# microcontroller.net
KiCad netlist of a schematic drawn in Altium Designer
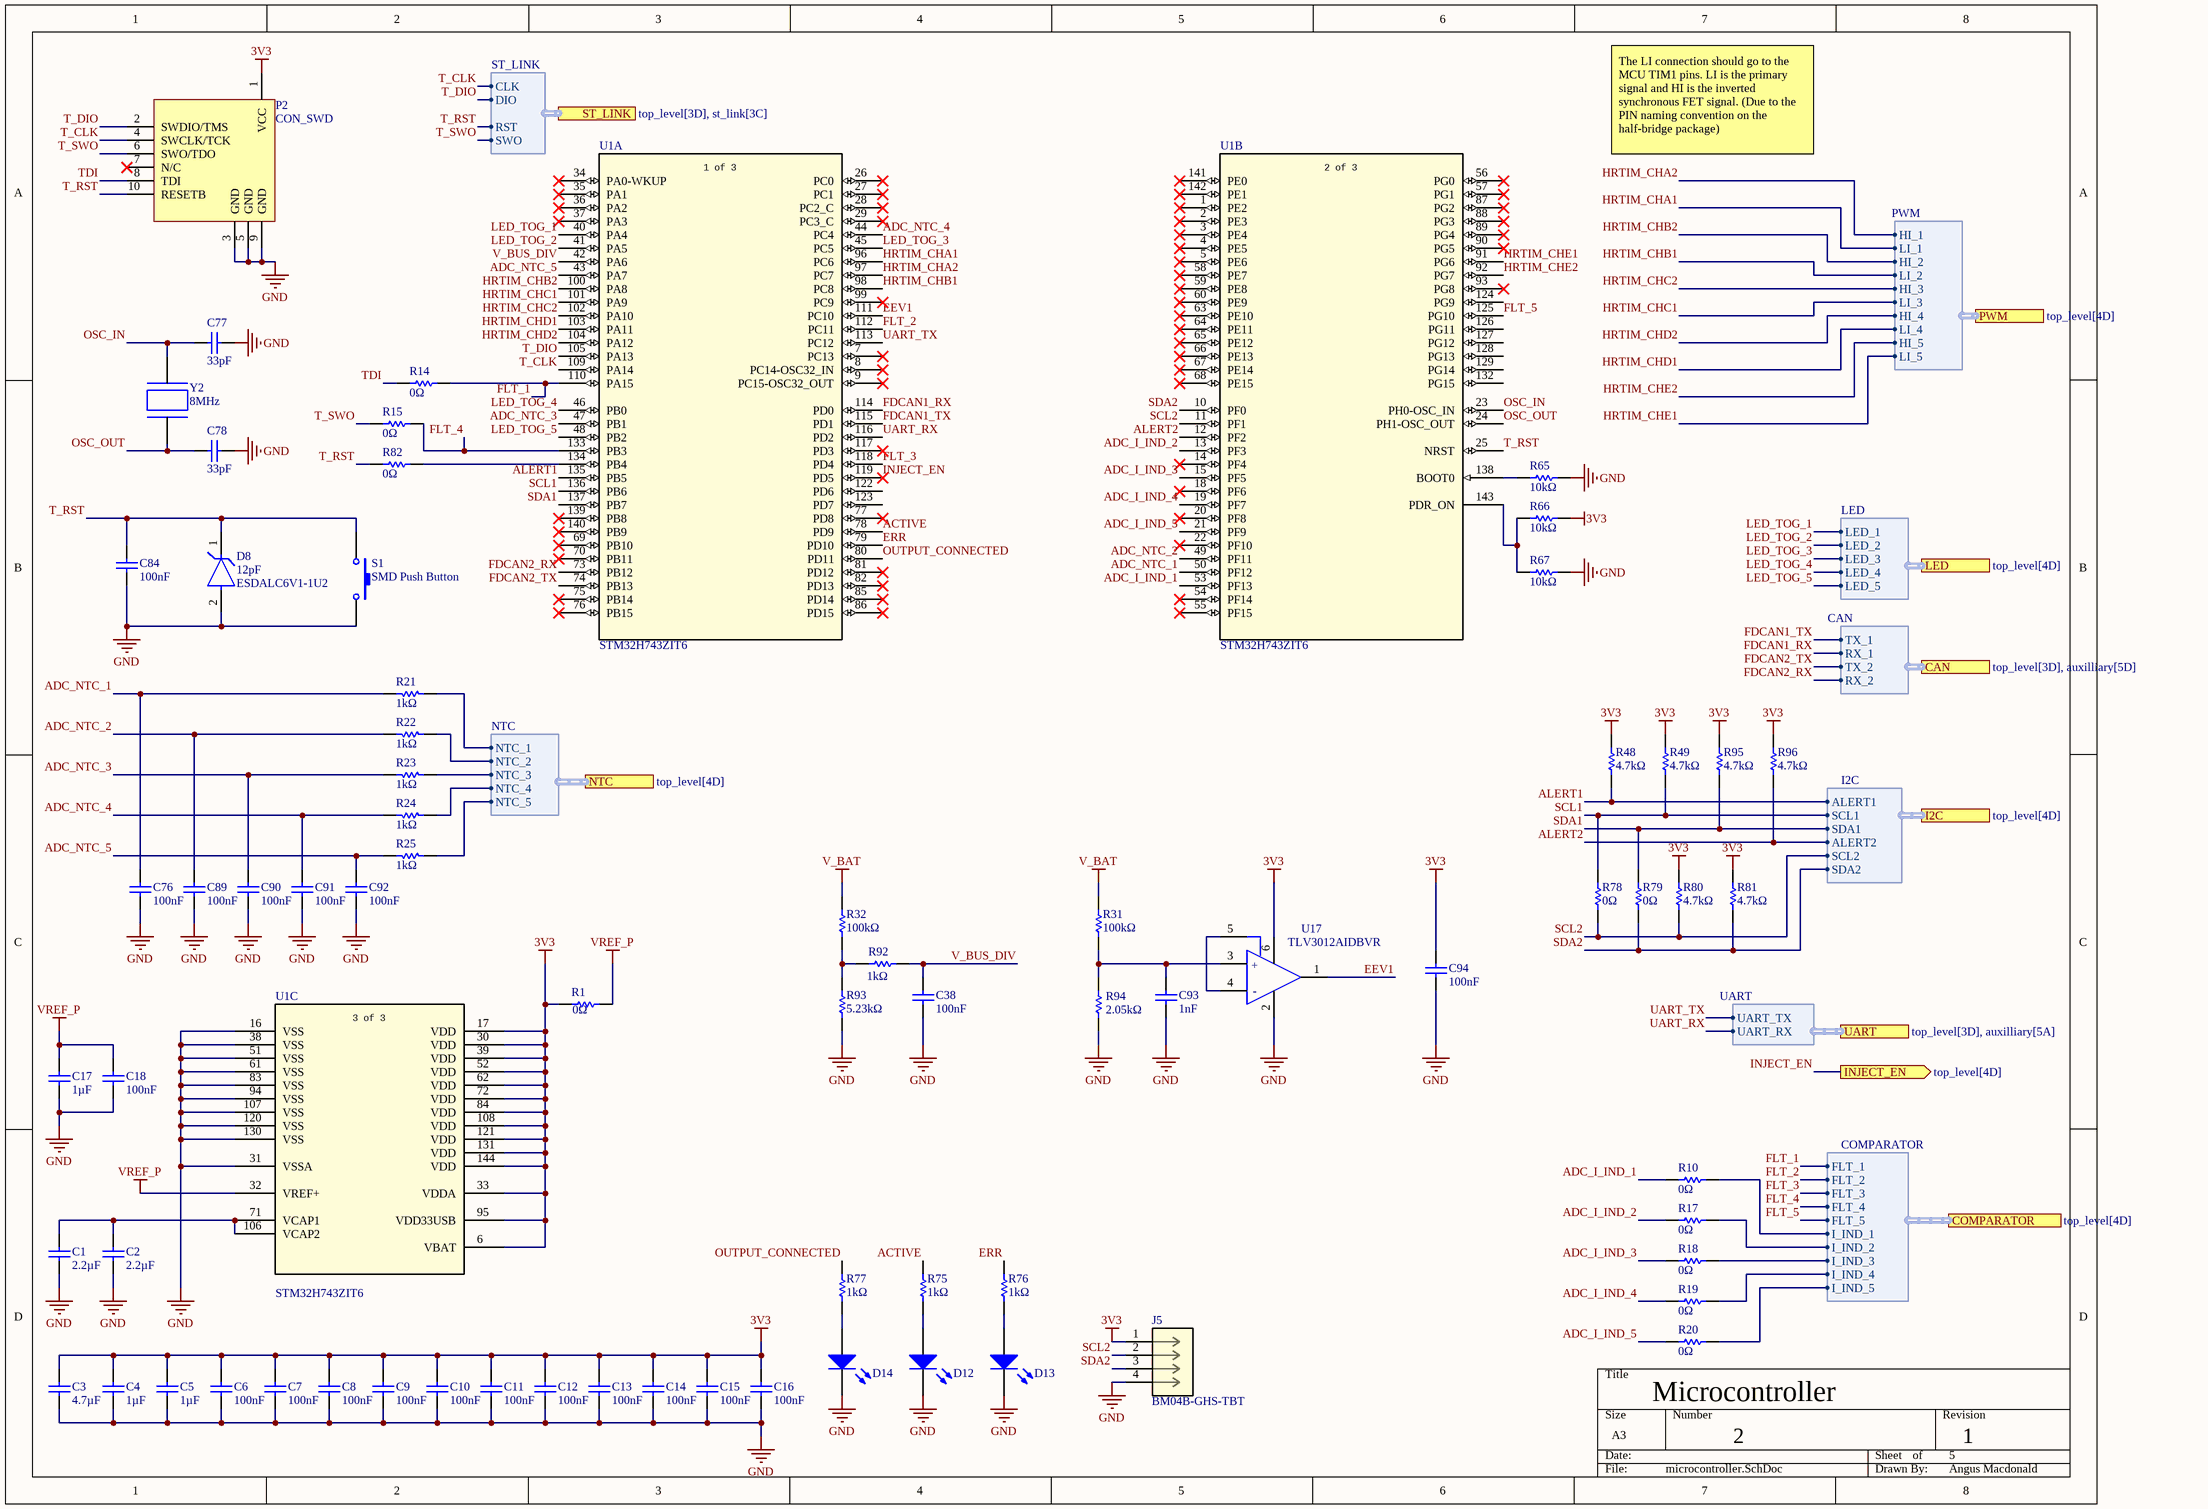
[diagram p0: microcontroller.SchDoc]

(export (version "E")
  (design (tool "Eeschema 10.0.6"))
  (components
    (comp (ref "C1")
      (value "2.2µF")
      (footprint "C0603")
      (description "6.3V 2.2uF X7R ±10% 0603 Multilayer Ceramic Capacitors MLCC - SMD/SMT ROHS")
      (fields (field (name "TOLERANCE") "10%") (field (name "Comment") "CC0603KRX7R5BB225"))
      (libsource (lib "Sunswift Racing") (part "Capacitor"))
    )
    (comp (ref "C2")
      (value "2.2µF")
      (footprint "C0603")
      (description "6.3V 2.2uF X7R ±10% 0603 Multilayer Ceramic Capacitors MLCC - SMD/SMT ROHS")
      (fields (field (name "TOLERANCE") "10%") (field (name "Comment") "CC0603KRX7R5BB225"))
      (libsource (lib "Sunswift Racing") (part "Capacitor"))
    )
    (comp (ref "C3")
      (value "4.7µF")
      (footprint "C0603")
      (description "Multilayer Ceramic Capacitors MLCC - SMD/SMT 6.3V 4.7uF X7R 0603 20%")
      (fields (field (name "TOLERANCE") "20%") (field (name "Comment") "CC0603MRX7R5BB475"))
      (libsource (lib "Sunswift Racing") (part "Capacitor"))
    )
    (comp (ref "C4")
      (value "1µF")
      (footprint "C0603")
      (description "16V 1uF X7R ±10% 0603 Multilayer Ceramic Capacitors MLCC - SMD/SMT ROHS")
      (fields (field (name "VOLTAGE") "16V") (field (name "TOLERANCE") "10%"))
      (libsource (lib "Sunswift Racing") (part "Capacitor"))
    )
    (comp (ref "C5")
      (value "1µF")
      (footprint "C0603")
      (description "16V 1uF X7R ±10% 0603 Multilayer Ceramic Capacitors MLCC - SMD/SMT ROHS")
      (fields (field (name "VOLTAGE") "16V") (field (name "TOLERANCE") "10%"))
      (libsource (lib "Sunswift Racing") (part "Capacitor"))
    )
    (comp (ref "C6")
      (value "100nF")
      (footprint "C0603")
      (description "25V 100nF X7R ±10% 0603 Multilayer Ceramic Capacitors MLCC - SMD/SMT ROHS")
      (fields (field (name "TOLERANCE") "10%") (field (name "VOLTAGE") "25V"))
      (libsource (lib "Sunswift Racing") (part "Capacitor"))
    )
    (comp (ref "C7")
      (value "100nF")
      (footprint "C0603")
      (description "25V 100nF X7R ±10% 0603 Multilayer Ceramic Capacitors MLCC - SMD/SMT ROHS")
      (fields (field (name "TOLERANCE") "10%") (field (name "VOLTAGE") "25V"))
      (libsource (lib "Sunswift Racing") (part "Capacitor"))
    )
    (comp (ref "C8")
      (value "100nF")
      (footprint "C0603")
      (description "25V 100nF X7R ±10% 0603 Multilayer Ceramic Capacitors MLCC - SMD/SMT ROHS")
      (fields (field (name "TOLERANCE") "10%") (field (name "VOLTAGE") "25V"))
      (libsource (lib "Sunswift Racing") (part "Capacitor"))
    )
    (comp (ref "C9")
      (value "100nF")
      (footprint "C0603")
      (description "25V 100nF X7R ±10% 0603 Multilayer Ceramic Capacitors MLCC - SMD/SMT ROHS")
      (fields (field (name "TOLERANCE") "10%") (field (name "VOLTAGE") "25V"))
      (libsource (lib "Sunswift Racing") (part "Capacitor"))
    )
    (comp (ref "C10")
      (value "100nF")
      (footprint "C0603")
      (description "25V 100nF X7R ±10% 0603 Multilayer Ceramic Capacitors MLCC - SMD/SMT ROHS")
      (fields (field (name "TOLERANCE") "10%") (field (name "VOLTAGE") "25V"))
      (libsource (lib "Sunswift Racing") (part "Capacitor"))
    )
    (comp (ref "C11")
      (value "100nF")
      (footprint "C0603")
      (description "25V 100nF X7R ±10% 0603 Multilayer Ceramic Capacitors MLCC - SMD/SMT ROHS")
      (fields (field (name "TOLERANCE") "10%") (field (name "VOLTAGE") "25V"))
      (libsource (lib "Sunswift Racing") (part "Capacitor"))
    )
    (comp (ref "C12")
      (value "100nF")
      (footprint "C0603")
      (description "25V 100nF X7R ±10% 0603 Multilayer Ceramic Capacitors MLCC - SMD/SMT ROHS")
      (fields (field (name "TOLERANCE") "10%") (field (name "VOLTAGE") "25V"))
      (libsource (lib "Sunswift Racing") (part "Capacitor"))
    )
    (comp (ref "C13")
      (value "100nF")
      (footprint "C0603")
      (description "25V 100nF X7R ±10% 0603 Multilayer Ceramic Capacitors MLCC - SMD/SMT ROHS")
      (fields (field (name "TOLERANCE") "10%") (field (name "VOLTAGE") "25V"))
      (libsource (lib "Sunswift Racing") (part "Capacitor"))
    )
    (comp (ref "C14")
      (value "100nF")
      (footprint "C0603")
      (description "25V 100nF X7R ±10% 0603 Multilayer Ceramic Capacitors MLCC - SMD/SMT ROHS")
      (fields (field (name "TOLERANCE") "10%") (field (name "VOLTAGE") "25V"))
      (libsource (lib "Sunswift Racing") (part "Capacitor"))
    )
    (comp (ref "C15")
      (value "100nF")
      (footprint "C0603")
      (description "25V 100nF X7R ±10% 0603 Multilayer Ceramic Capacitors MLCC - SMD/SMT ROHS")
      (fields (field (name "TOLERANCE") "10%") (field (name "VOLTAGE") "25V"))
      (libsource (lib "Sunswift Racing") (part "Capacitor"))
    )
    (comp (ref "C16")
      (value "100nF")
      (footprint "C0603")
      (description "25V 100nF X7R ±10% 0603 Multilayer Ceramic Capacitors MLCC - SMD/SMT ROHS")
      (fields (field (name "TOLERANCE") "10%") (field (name "VOLTAGE") "25V"))
      (libsource (lib "Sunswift Racing") (part "Capacitor"))
    )
    (comp (ref "C17")
      (value "1µF")
      (footprint "C0603")
      (description "16V 1uF X7R ±10% 0603 Multilayer Ceramic Capacitors MLCC - SMD/SMT ROHS")
      (fields (field (name "VOLTAGE") "16V") (field (name "TOLERANCE") "10%"))
      (libsource (lib "Sunswift Racing") (part "Capacitor"))
    )
    (comp (ref "C18")
      (value "100nF")
      (footprint "C0603")
      (description "25V 100nF X7R ±10% 0603 Multilayer Ceramic Capacitors MLCC - SMD/SMT ROHS")
      (fields (field (name "TOLERANCE") "10%") (field (name "VOLTAGE") "25V"))
      (libsource (lib "Sunswift Racing") (part "Capacitor"))
    )
    (comp (ref "C38")
      (value "100nF")
      (footprint "C0603")
      (description "25V 100nF X7R ±10% 0603 Multilayer Ceramic Capacitors MLCC - SMD/SMT ROHS")
      (fields (field (name "TOLERANCE") "10%") (field (name "VOLTAGE") "25V"))
      (libsource (lib "Sunswift Racing") (part "Capacitor"))
    )
    (comp (ref "C76")
      (value "100nF")
      (footprint "C0603")
      (description "25V 100nF X7R ±10% 0603 Multilayer Ceramic Capacitors MLCC - SMD/SMT ROHS")
      (fields (field (name "TOLERANCE") "10%") (field (name "VOLTAGE") "25V"))
      (libsource (lib "Sunswift Racing") (part "Capacitor"))
    )
    (comp (ref "C77")
      (value "33pF")
      (footprint "C0603")
      (description "0603 33 pF 50 V ±5 % Tolerance C0G/NP0 SMT Multilayer Ceramic Capacitor")
      (fields (field (name "TOLERANCE") "5%") (field (name "Comment") "CC0603JPNPO9BN330"))
      (libsource (lib "Sunswift Racing") (part "Capacitor"))
    )
    (comp (ref "C78")
      (value "33pF")
      (footprint "C0603")
      (description "0603 33 pF 50 V ±5 % Tolerance C0G/NP0 SMT Multilayer Ceramic Capacitor")
      (fields (field (name "TOLERANCE") "5%") (field (name "Comment") "CC0603JPNPO9BN330"))
      (libsource (lib "Sunswift Racing") (part "Capacitor"))
    )
    (comp (ref "C84")
      (value "100nF")
      (footprint "C0603")
      (description "25V 100nF X7R ±10% 0603 Multilayer Ceramic Capacitors MLCC - SMD/SMT ROHS")
      (fields (field (name "TOLERANCE") "10%") (field (name "VOLTAGE") "25V"))
      (libsource (lib "Sunswift Racing") (part "Capacitor"))
    )
    (comp (ref "C89")
      (value "100nF")
      (footprint "C0603")
      (description "25V 100nF X7R ±10% 0603 Multilayer Ceramic Capacitors MLCC - SMD/SMT ROHS")
      (fields (field (name "TOLERANCE") "10%") (field (name "VOLTAGE") "25V"))
      (libsource (lib "Sunswift Racing") (part "Capacitor"))
    )
    (comp (ref "C90")
      (value "100nF")
      (footprint "C0603")
      (description "25V 100nF X7R ±10% 0603 Multilayer Ceramic Capacitors MLCC - SMD/SMT ROHS")
      (fields (field (name "TOLERANCE") "10%") (field (name "VOLTAGE") "25V"))
      (libsource (lib "Sunswift Racing") (part "Capacitor"))
    )
    (comp (ref "C91")
      (value "100nF")
      (footprint "C0603")
      (description "25V 100nF X7R ±10% 0603 Multilayer Ceramic Capacitors MLCC - SMD/SMT ROHS")
      (fields (field (name "TOLERANCE") "10%") (field (name "VOLTAGE") "25V"))
      (libsource (lib "Sunswift Racing") (part "Capacitor"))
    )
    (comp (ref "C92")
      (value "100nF")
      (footprint "C0603")
      (description "25V 100nF X7R ±10% 0603 Multilayer Ceramic Capacitors MLCC - SMD/SMT ROHS")
      (fields (field (name "TOLERANCE") "10%") (field (name "VOLTAGE") "25V"))
      (libsource (lib "Sunswift Racing") (part "Capacitor"))
    )
    (comp (ref "C93")
      (value "1nF")
      (footprint "C0603")
      (description "Surface Mount Ceramic Multilayer Capacitor 0.001uF 10% X7R 50V 0603 Paper T/R")
      (fields (field (name "VOLTAGE") "50V") (field (name "TOLERANCE") "10%"))
      (libsource (lib "Sunswift Racing") (part "Capacitor"))
    )
    (comp (ref "C94")
      (value "100nF")
      (footprint "C0603")
      (description "25V 100nF X7R ±10% 0603 Multilayer Ceramic Capacitors MLCC - SMD/SMT ROHS")
      (fields (field (name "TOLERANCE") "10%") (field (name "VOLTAGE") "25V"))
      (libsource (lib "Sunswift Racing") (part "Capacitor"))
    )
    (comp (ref "D8")
      (value "ESDALC6V1-1U2")
      (footprint "FP-ST0201-MFG")
      (description "20W 6.1V 6.1V 3V 0201 ESD and Surge Protection (TVS/ESD) ROHS")
      (fields (field (name "ALTIUM_VALUE") "12pF"))
      (libsource (lib "Sunswift Racing") (part "f813f71cba58e380607f5dd3caf9714"))
    )
    (comp (ref "D12")
      (value "LED EMERALD 0805")
      (footprint "0805 LED")
      (description "Emerald 0805  Light Emitting Diodes (LED) ROHS GREEN JLCPCB PICK&PLACE")
      (fields (field (name "MFR.PART #") "C2297") (field (name "MANUFACTURER") "Hubei KENTO Elec"))
      (libsource (lib "Sunswift Racing") (part "LED 0805-Symbol-1"))
    )
    (comp (ref "D13")
      (value "LED RED 0805")
      (footprint "0805 LED")
      (description "Red 0805  Light Emitting Diodes (LED) ROHS JLCPCB PICK&PLACE")
      (fields
        (field (name "MANUFACTURER") "Foshan NationStar Optoelectronics")
        (field (name "JLCPCB PART #") "C84256")
      )
      (libsource (lib "Sunswift Racing") (part "LED 0805-Symbol-1"))
    )
    (comp (ref "D14")
      (value "LED EMERALD 0805")
      (footprint "0805 LED")
      (description "Emerald 0805  Light Emitting Diodes (LED) ROHS GREEN JLCPCB PICK&PLACE")
      (fields (field (name "MFR.PART #") "C2297") (field (name "MANUFACTURER") "Hubei KENTO Elec"))
      (libsource (lib "Sunswift Racing") (part "LED 0805-Symbol-1"))
    )
    (comp (ref "J5")
      (value "BM04B-GHS-TBT")
      (footprint "CONN_BM04B-GHS-TBT_JST")
      (description "Description")
      (fields (field (name "COPYRIGHT") "Copyright (C) 2026 Ultra Librarian. All rights reserved."))
      (libsource (lib "Sunswift Racing") (part "BM04B-GHS-TBT"))
    )
    (comp (ref "P2")
      (value "CON_SWD")
      (footprint "SMD, P=1.27mm")
      (description "ARM Coresight 10 Header")
      (fields
        (field (name "JLCPCB PART #") "C5250218")
        (field (name "MANUFACTURER PART NUMBER") "3220-10-0300-00")
      )
      (libsource (lib "Sunswift Racing") (part "CoreSight 10-pin Connector"))
    )
    (comp (ref "R1")
      (value "0Ω")
      (footprint "RESC1608X55X25ML10T15")
      (description "GENERAL PURPOSE CHIP RESISTOR Metal Glaze/thick Film, 0.1W, 0ohm, Surface Mount, 0603")
      (fields (field (name "TOLERANCE") "1%") (field (name "Comment") "RC0603JR-070RL"))
      (libsource (lib "Sunswift Racing") (part "RES-2"))
    )
    (comp (ref "R10")
      (value "0Ω")
      (footprint "RESC1608X55X25ML10T15")
      (description "GENERAL PURPOSE CHIP RESISTOR Metal Glaze/thick Film, 0.1W, 0ohm, Surface Mount, 0603")
      (fields (field (name "TOLERANCE") "1%") (field (name "Comment") "RC0603JR-070RL"))
      (libsource (lib "Sunswift Racing") (part "RES-2"))
    )
    (comp (ref "R14")
      (value "0Ω")
      (footprint "RESC1608X55X25ML10T15")
      (description "GENERAL PURPOSE CHIP RESISTOR Metal Glaze/thick Film, 0.1W, 0ohm, Surface Mount, 0603")
      (fields (field (name "TOLERANCE") "1%") (field (name "Comment") "RC0603JR-070RL"))
      (libsource (lib "Sunswift Racing") (part "RES-2"))
    )
    (comp (ref "R15")
      (value "0Ω")
      (footprint "RESC1608X55X25ML10T15")
      (description "GENERAL PURPOSE CHIP RESISTOR Metal Glaze/thick Film, 0.1W, 0ohm, Surface Mount, 0603")
      (fields (field (name "TOLERANCE") "1%") (field (name "Comment") "RC0603JR-070RL"))
      (libsource (lib "Sunswift Racing") (part "RES-2"))
    )
    (comp (ref "R17")
      (value "0Ω")
      (footprint "RESC1608X55X25ML10T15")
      (description "GENERAL PURPOSE CHIP RESISTOR Metal Glaze/thick Film, 0.1W, 0ohm, Surface Mount, 0603")
      (fields (field (name "TOLERANCE") "1%") (field (name "Comment") "RC0603JR-070RL"))
      (libsource (lib "Sunswift Racing") (part "RES-2"))
    )
    (comp (ref "R18")
      (value "0Ω")
      (footprint "RESC1608X55X25ML10T15")
      (description "GENERAL PURPOSE CHIP RESISTOR Metal Glaze/thick Film, 0.1W, 0ohm, Surface Mount, 0603")
      (fields (field (name "TOLERANCE") "1%") (field (name "Comment") "RC0603JR-070RL"))
      (libsource (lib "Sunswift Racing") (part "RES-2"))
    )
    (comp (ref "R19")
      (value "0Ω")
      (footprint "RESC1608X55X25ML10T15")
      (description "GENERAL PURPOSE CHIP RESISTOR Metal Glaze/thick Film, 0.1W, 0ohm, Surface Mount, 0603")
      (fields (field (name "TOLERANCE") "1%") (field (name "Comment") "RC0603JR-070RL"))
      (libsource (lib "Sunswift Racing") (part "RES-2"))
    )
    (comp (ref "R20")
      (value "0Ω")
      (footprint "RESC1608X55X25ML10T15")
      (description "GENERAL PURPOSE CHIP RESISTOR Metal Glaze/thick Film, 0.1W, 0ohm, Surface Mount, 0603")
      (fields (field (name "TOLERANCE") "1%") (field (name "Comment") "RC0603JR-070RL"))
      (libsource (lib "Sunswift Racing") (part "RES-2"))
    )
    (comp (ref "R21")
      (value "1kΩ")
      (footprint "RESC1608X55X25ML10T15")
      (description "1 kOhms ±1% 0.1W, 1/10W Chip Resistor 0603 (1608 Metric) Moisture Resistant Thick Film")
      (fields (field (name "TOLERANCE") "1%") (field (name "Comment") "RC0603FR-101KL"))
      (libsource (lib "Sunswift Racing") (part "RES-2"))
    )
    (comp (ref "R22")
      (value "1kΩ")
      (footprint "RESC1608X55X25ML10T15")
      (description "1 kOhms ±1% 0.1W, 1/10W Chip Resistor 0603 (1608 Metric) Moisture Resistant Thick Film")
      (fields (field (name "TOLERANCE") "1%") (field (name "Comment") "RC0603FR-101KL"))
      (libsource (lib "Sunswift Racing") (part "RES-2"))
    )
    (comp (ref "R23")
      (value "1kΩ")
      (footprint "RESC1608X55X25ML10T15")
      (description "1 kOhms ±1% 0.1W, 1/10W Chip Resistor 0603 (1608 Metric) Moisture Resistant Thick Film")
      (fields (field (name "TOLERANCE") "1%") (field (name "Comment") "RC0603FR-101KL"))
      (libsource (lib "Sunswift Racing") (part "RES-2"))
    )
    (comp (ref "R24")
      (value "1kΩ")
      (footprint "RESC1608X55X25ML10T15")
      (description "1 kOhms ±1% 0.1W, 1/10W Chip Resistor 0603 (1608 Metric) Moisture Resistant Thick Film")
      (fields (field (name "TOLERANCE") "1%") (field (name "Comment") "RC0603FR-101KL"))
      (libsource (lib "Sunswift Racing") (part "RES-2"))
    )
    (comp (ref "R25")
      (value "1kΩ")
      (footprint "RESC1608X55X25ML10T15")
      (description "1 kOhms ±1% 0.1W, 1/10W Chip Resistor 0603 (1608 Metric) Moisture Resistant Thick Film")
      (fields (field (name "TOLERANCE") "1%") (field (name "Comment") "RC0603FR-101KL"))
      (libsource (lib "Sunswift Racing") (part "RES-2"))
    )
    (comp (ref "R31")
      (value "100kΩ")
      (footprint "RESC1608X55X25ML10T15")
      (description "Res General Purpose Thick Film 0603 100k Ohm 1% 1/10W ±100ppm/°C Molded Paper T/R")
      (fields (field (name "TOLERANCE") "1%") (field (name "Comment") "RC0603FR-07100KL"))
      (libsource (lib "Sunswift Racing") (part "RES-2"))
    )
    (comp (ref "R32")
      (value "100kΩ")
      (footprint "RESC1608X55X25ML10T15")
      (description "Res General Purpose Thick Film 0603 100k Ohm 1% 1/10W ±100ppm/°C Molded Paper T/R")
      (fields (field (name "TOLERANCE") "1%") (field (name "Comment") "RC0603FR-07100KL"))
      (libsource (lib "Sunswift Racing") (part "RES-2"))
    )
    (comp (ref "R48")
      (value "4.7kΩ")
      (footprint "RESC1608X55X25ML10T15")
      (description "Yageo RC0603FR-074K7L Resistor 0603 SMD 4.7k Ohm 1% 100mW Thick Film")
      (fields (field (name "TOLERANCE") "1%") (field (name "Comment") "RC0603FR-074K7L"))
      (libsource (lib "Sunswift Racing") (part "RES-2"))
    )
    (comp (ref "R49")
      (value "4.7kΩ")
      (footprint "RESC1608X55X25ML10T15")
      (description "Yageo RC0603FR-074K7L Resistor 0603 SMD 4.7k Ohm 1% 100mW Thick Film")
      (fields (field (name "TOLERANCE") "1%") (field (name "Comment") "RC0603FR-074K7L"))
      (libsource (lib "Sunswift Racing") (part "RES-2"))
    )
    (comp (ref "R65")
      (value "10kΩ")
      (footprint "RESC1608X55X25ML10T15")
      (description "10 kOhms ±1% 0.1W, 1/10W Chip Resistor 0603 (1608 Metric) Moisture Resistant Thick Film")
      (fields (field (name "TOLERANCE") "1%") (field (name "Comment") "RC0603FR-0710KL"))
      (libsource (lib "Sunswift Racing") (part "RES-2"))
    )
    (comp (ref "R66")
      (value "10kΩ")
      (footprint "RESC1608X55X25ML10T15")
      (description "10 kOhms ±1% 0.1W, 1/10W Chip Resistor 0603 (1608 Metric) Moisture Resistant Thick Film")
      (fields (field (name "TOLERANCE") "1%") (field (name "Comment") "RC0603FR-0710KL"))
      (libsource (lib "Sunswift Racing") (part "RES-2"))
    )
    (comp (ref "R67")
      (value "10kΩ")
      (footprint "RESC1608X55X25ML10T15")
      (description "10 kOhms ±1% 0.1W, 1/10W Chip Resistor 0603 (1608 Metric) Moisture Resistant Thick Film")
      (fields (field (name "TOLERANCE") "1%") (field (name "Comment") "RC0603FR-0710KL"))
      (libsource (lib "Sunswift Racing") (part "RES-2"))
    )
    (comp (ref "R75")
      (value "1kΩ")
      (footprint "RESC1608X55X25ML10T15")
      (description "1 kOhms ±1% 0.1W, 1/10W Chip Resistor 0603 (1608 Metric) Moisture Resistant Thick Film")
      (fields (field (name "TOLERANCE") "1%") (field (name "Comment") "RC0603FR-101KL"))
      (libsource (lib "Sunswift Racing") (part "RES-2"))
    )
    (comp (ref "R76")
      (value "1kΩ")
      (footprint "RESC1608X55X25ML10T15")
      (description "1 kOhms ±1% 0.1W, 1/10W Chip Resistor 0603 (1608 Metric) Moisture Resistant Thick Film")
      (fields (field (name "TOLERANCE") "1%") (field (name "Comment") "RC0603FR-101KL"))
      (libsource (lib "Sunswift Racing") (part "RES-2"))
    )
    (comp (ref "R77")
      (value "1kΩ")
      (footprint "RESC1608X55X25ML10T15")
      (description "1 kOhms ±1% 0.1W, 1/10W Chip Resistor 0603 (1608 Metric) Moisture Resistant Thick Film")
      (fields (field (name "TOLERANCE") "1%") (field (name "Comment") "RC0603FR-101KL"))
      (libsource (lib "Sunswift Racing") (part "RES-2"))
    )
    (comp (ref "R78")
      (value "0Ω")
      (footprint "RESC1608X55X25ML10T15")
      (description "GENERAL PURPOSE CHIP RESISTOR Metal Glaze/thick Film, 0.1W, 0ohm, Surface Mount, 0603")
      (fields (field (name "TOLERANCE") "1%") (field (name "Comment") "RC0603JR-070RL"))
      (libsource (lib "Sunswift Racing") (part "RES-2"))
    )
    (comp (ref "R79")
      (value "0Ω")
      (footprint "RESC1608X55X25ML10T15")
      (description "GENERAL PURPOSE CHIP RESISTOR Metal Glaze/thick Film, 0.1W, 0ohm, Surface Mount, 0603")
      (fields (field (name "TOLERANCE") "1%") (field (name "Comment") "RC0603JR-070RL"))
      (libsource (lib "Sunswift Racing") (part "RES-2"))
    )
    (comp (ref "R80")
      (value "4.7kΩ")
      (footprint "RESC1608X55X25ML10T15")
      (description "Yageo RC0603FR-074K7L Resistor 0603 SMD 4.7k Ohm 1% 100mW Thick Film")
      (fields (field (name "TOLERANCE") "1%") (field (name "Comment") "RC0603FR-074K7L"))
      (libsource (lib "Sunswift Racing") (part "RES-2"))
    )
    (comp (ref "R81")
      (value "4.7kΩ")
      (footprint "RESC1608X55X25ML10T15")
      (description "Yageo RC0603FR-074K7L Resistor 0603 SMD 4.7k Ohm 1% 100mW Thick Film")
      (fields (field (name "TOLERANCE") "1%") (field (name "Comment") "RC0603FR-074K7L"))
      (libsource (lib "Sunswift Racing") (part "RES-2"))
    )
    (comp (ref "R82")
      (value "0Ω")
      (footprint "RESC1608X55X25ML10T15")
      (description "GENERAL PURPOSE CHIP RESISTOR Metal Glaze/thick Film, 0.1W, 0ohm, Surface Mount, 0603")
      (fields (field (name "TOLERANCE") "1%") (field (name "Comment") "RC0603JR-070RL"))
      (libsource (lib "Sunswift Racing") (part "RES-2"))
    )
    (comp (ref "R92")
      (value "1kΩ")
      (footprint "RESC1608X55X25ML10T15")
      (description "1 kOhms ±1% 0.1W, 1/10W Chip Resistor 0603 (1608 Metric) Moisture Resistant Thick Film")
      (fields (field (name "TOLERANCE") "1%") (field (name "Comment") "RC0603FR-101KL"))
      (libsource (lib "Sunswift Racing") (part "RES-2"))
    )
    (comp (ref "R93")
      (value "5.23kΩ")
      (footprint "RESC1608X55X25ML10T15")
      (description "0603 5.23K ohms 1% thick film surface mount chip resistor")
      (fields (field (name "TOLERANCE") "1%") (field (name "Comment") "RC0603FR-135K23L"))
      (libsource (lib "Sunswift Racing") (part "RES-2"))
    )
    (comp (ref "R94")
      (value "2.05kΩ")
      (footprint "RESC1608X55X25ML10T15")
      (description "100mW Thick Film Resistors 75V ±100ppm/℃ ±1% 2.05kΩ 0603 Chip Resistor - Surface Mount ROHS")
      (fields (field (name "TOLERANCE") "1%") (field (name "Comment") "RC0603FR-072K05L"))
      (libsource (lib "Sunswift Racing") (part "RES-2"))
    )
    (comp (ref "R95")
      (value "4.7kΩ")
      (footprint "RESC1608X55X25ML10T15")
      (description "Yageo RC0603FR-074K7L Resistor 0603 SMD 4.7k Ohm 1% 100mW Thick Film")
      (fields (field (name "TOLERANCE") "1%") (field (name "Comment") "RC0603FR-074K7L"))
      (libsource (lib "Sunswift Racing") (part "RES-2"))
    )
    (comp (ref "R96")
      (value "4.7kΩ")
      (footprint "RESC1608X55X25ML10T15")
      (description "Yageo RC0603FR-074K7L Resistor 0603 SMD 4.7k Ohm 1% 100mW Thick Film")
      (fields (field (name "TOLERANCE") "1%") (field (name "Comment") "RC0603FR-074K7L"))
      (libsource (lib "Sunswift Racing") (part "RES-2"))
    )
    (comp (ref "S1")
      (value "SMD Push Button")
      (footprint "SMD Push Button-Footprint-1")
      (description "Tactile Switches SPST Rnd Bttn Gull .05A 32VDC 1W SMD")
      (fields (field (name "MANUFACTURER PART NUMBER") "KMR221GLFS") (field (name "JLCPCB PART #") "C72443"))
      (libsource (lib "Sunswift Racing") (part "SW-PB"))
    )
    (comp (ref "U1")
      (value "STM32H743ZIT6")
      (footprint "LQFP144-20x20mm")
      (fields (field (name "COPYRIGHT") "Copyright (C) 2025 Ultra Librarian. All rights reserved."))
      (libsource (lib "Sunswift Racing") (part "STM32H743ZIT6"))
    )
    (comp (ref "U17")
      (value "TLV3012AIDBVR")
      (footprint "FP-DBV0006A-IPC_B")
      (description "Low-power comparator with reference (push-pull) 6-SOT-23 -40 to 125")
      (libsource (lib "Sunswift Racing") (part "c4a04de7fcb83ef995881f343e5bdea"))
    )
    (comp (ref "Y2")
      (value "X50328MSB2GI")
      (footprint "RESC5032X135N")
      (description "8MHz 20pF ±10ppm SMD5032-2P Crystals ROHS JLCPCB PICK&PLACE")
      (fields
        (field (name "MANUFACTURER") "Yangxing Tech")
        (field (name "JLCPCB PART #") "C115962")
        (field (name "FREQUENCY") "8MHz")
      )
      (libsource (lib "Sunswift Racing") (part "X50328MSB2GI-Symbol-1"))
    )
  )
  (nets
    (net (code "9") (name "/ACTIVE") (class "Default")
      (node (ref "R75") (pin "1") (pinfunction "1_1") (pintype "passive"))
      (node (ref "U1") (pin "78") (pinfunction "PD9_78") (pintype "bidirectional"))
    )
    (net (code "10") (name "/ADC_I_IND_1") (class "Default")
      (node (ref "R10") (pin "2") (pinfunction "2_2") (pintype "passive"))
      (node (ref "U1") (pin "53") (pinfunction "PF13_53") (pintype "bidirectional"))
    )
    (net (code "11") (name "/ADC_I_IND_2") (class "Default")
      (node (ref "R17") (pin "2") (pinfunction "2_2") (pintype "passive"))
      (node (ref "U1") (pin "13") (pinfunction "PF3_13") (pintype "bidirectional"))
    )
    (net (code "12") (name "/ADC_I_IND_3") (class "Default")
      (node (ref "R18") (pin "2") (pinfunction "2_2") (pintype "passive"))
      (node (ref "U1") (pin "15") (pinfunction "PF5_15") (pintype "bidirectional"))
    )
    (net (code "13") (name "/ADC_I_IND_4") (class "Default")
      (node (ref "R19") (pin "2") (pinfunction "2_2") (pintype "passive"))
      (node (ref "U1") (pin "19") (pinfunction "PF7_19") (pintype "bidirectional"))
    )
    (net (code "14") (name "/ADC_I_IND_5") (class "Default")
      (node (ref "R20") (pin "2") (pinfunction "2_2") (pintype "passive"))
      (node (ref "U1") (pin "21") (pinfunction "PF9_21") (pintype "bidirectional"))
    )
    (net (code "15") (name "/ADC_NTC_1") (class "Default")
      (node (ref "C76") (pin "2") (pinfunction "2_2") (pintype "passive"))
      (node (ref "R21") (pin "2") (pinfunction "2_2") (pintype "passive"))
      (node (ref "U1") (pin "50") (pinfunction "PF12_50") (pintype "bidirectional"))
    )
    (net (code "16") (name "/ADC_NTC_2") (class "Default")
      (node (ref "C89") (pin "2") (pinfunction "2_2") (pintype "passive"))
      (node (ref "R22") (pin "2") (pinfunction "2_2") (pintype "passive"))
      (node (ref "U1") (pin "49") (pinfunction "PF11_49") (pintype "bidirectional"))
    )
    (net (code "17") (name "/ADC_NTC_3") (class "Default")
      (node (ref "C90") (pin "2") (pinfunction "2_2") (pintype "passive"))
      (node (ref "R23") (pin "2") (pinfunction "2_2") (pintype "passive"))
      (node (ref "U1") (pin "47") (pinfunction "PB1_47") (pintype "bidirectional"))
    )
    (net (code "18") (name "/ADC_NTC_4") (class "Default")
      (node (ref "C91") (pin "2") (pinfunction "2_2") (pintype "passive"))
      (node (ref "R24") (pin "2") (pinfunction "2_2") (pintype "passive"))
      (node (ref "U1") (pin "44") (pinfunction "PC4_44") (pintype "bidirectional"))
    )
    (net (code "19") (name "/ADC_NTC_5") (class "Default")
      (node (ref "C92") (pin "2") (pinfunction "2_2") (pintype "passive"))
      (node (ref "R25") (pin "2") (pinfunction "2_2") (pintype "passive"))
      (node (ref "U1") (pin "43") (pinfunction "PA7_43") (pintype "bidirectional"))
    )
    (net (code "20") (name "/ALERT1") (class "Default")
      (node (ref "R48") (pin "1") (pinfunction "1_1") (pintype "passive"))
      (node (ref "U1") (pin "135") (pinfunction "PB5_135") (pintype "bidirectional"))
    )
    (net (code "21") (name "/ALERT2") (class "Default")
      (node (ref "R96") (pin "1") (pinfunction "1_1") (pintype "passive"))
      (node (ref "U1") (pin "12") (pinfunction "PF2_12") (pintype "bidirectional"))
    )
    (net (code "22") (name "/EEV1") (class "Default")
      (node (ref "U1") (pin "111") (pinfunction "PC10_111") (pintype "bidirectional"))
      (node (ref "U17") (pin "1") (pinfunction "OUT_1") (pintype "passive"))
    )
    (net (code "23") (name "/ERR") (class "Default")
      (node (ref "R76") (pin "2") (pinfunction "2_2") (pintype "passive"))
      (node (ref "U1") (pin "79") (pinfunction "PD10_79") (pintype "bidirectional"))
    )
    (net (code "24") (name "/FDCAN1_RX") (class "Default")
      (node (ref "U1") (pin "114") (pinfunction "PD0_114") (pintype "bidirectional"))
    )
    (net (code "25") (name "/FDCAN1_TX") (class "Default")
      (node (ref "U1") (pin "115") (pinfunction "PD1_115") (pintype "bidirectional"))
    )
    (net (code "26") (name "/FDCAN2_RX") (class "Default")
      (node (ref "U1") (pin "73") (pinfunction "PB12_73") (pintype "bidirectional"))
    )
    (net (code "27") (name "/FDCAN2_TX") (class "Default")
      (node (ref "U1") (pin "74") (pinfunction "PB13_74") (pintype "bidirectional"))
    )
    (net (code "28") (name "/FLT_1") (class "Default")
      (node (ref "R14") (pin "1") (pinfunction "1_1") (pintype "passive"))
      (node (ref "U1") (pin "110") (pinfunction "PA15_110") (pintype "bidirectional"))
    )
    (net (code "29") (name "/FLT_2") (class "Default")
      (node (ref "U1") (pin "112") (pinfunction "PC11_112") (pintype "bidirectional"))
    )
    (net (code "30") (name "/FLT_3") (class "Default")
      (node (ref "U1") (pin "118") (pinfunction "PD4_118") (pintype "bidirectional"))
    )
    (net (code "31") (name "/FLT_4") (class "Default")
      (node (ref "R15") (pin "1") (pinfunction "1_1") (pintype "passive"))
      (node (ref "U1") (pin "133") (pinfunction "PB3_133") (pintype "bidirectional"))
    )
    (net (code "32") (name "/FLT_5") (class "Default")
      (node (ref "U1") (pin "125") (pinfunction "PG10_125") (pintype "bidirectional"))
    )
    (net (code "33") (name "/HRTIM_CHA1") (class "Default")
      (node (ref "U1") (pin "96") (pinfunction "PC6_96") (pintype "bidirectional"))
    )
    (net (code "34") (name "/HRTIM_CHA2") (class "Default")
      (node (ref "U1") (pin "97") (pinfunction "PC7_97") (pintype "bidirectional"))
    )
    (net (code "35") (name "/HRTIM_CHB1") (class "Default")
      (node (ref "U1") (pin "98") (pinfunction "PC8_98") (pintype "bidirectional"))
    )
    (net (code "36") (name "/HRTIM_CHB2") (class "Default")
      (node (ref "U1") (pin "100") (pinfunction "PA8_100") (pintype "bidirectional"))
    )
    (net (code "37") (name "/HRTIM_CHC1") (class "Default")
      (node (ref "U1") (pin "101") (pinfunction "PA9_101") (pintype "bidirectional"))
    )
    (net (code "38") (name "/HRTIM_CHC2") (class "Default")
      (node (ref "U1") (pin "102") (pinfunction "PA10_102") (pintype "bidirectional"))
    )
    (net (code "39") (name "/HRTIM_CHD1") (class "Default")
      (node (ref "U1") (pin "103") (pinfunction "PA11_103") (pintype "bidirectional"))
    )
    (net (code "40") (name "/HRTIM_CHD2") (class "Default")
      (node (ref "U1") (pin "104") (pinfunction "PA12_104") (pintype "bidirectional"))
    )
    (net (code "41") (name "/HRTIM_CHE1") (class "Default")
      (node (ref "U1") (pin "91") (pinfunction "PG6_91") (pintype "bidirectional"))
    )
    (net (code "42") (name "/HRTIM_CHE2") (class "Default")
      (node (ref "U1") (pin "92") (pinfunction "PG7_92") (pintype "bidirectional"))
    )
    (net (code "43") (name "/INJECT_EN") (class "Default")
      (node (ref "U1") (pin "119") (pinfunction "PD5_119") (pintype "bidirectional+no_connect"))
    )
    (net (code "44") (name "/I_IND_1") (class "Default")
      (node (ref "R10") (pin "1") (pinfunction "1_1") (pintype "passive"))
    )
    (net (code "45") (name "/I_IND_2") (class "Default")
      (node (ref "R17") (pin "1") (pinfunction "1_1") (pintype "passive"))
    )
    (net (code "46") (name "/I_IND_3") (class "Default")
      (node (ref "R18") (pin "1") (pinfunction "1_1") (pintype "passive"))
    )
    (net (code "47") (name "/I_IND_4") (class "Default")
      (node (ref "R19") (pin "1") (pinfunction "1_1") (pintype "passive"))
    )
    (net (code "48") (name "/I_IND_5") (class "Default")
      (node (ref "R20") (pin "1") (pinfunction "1_1") (pintype "passive"))
    )
    (net (code "49") (name "/LED_TOG_1") (class "Default")
      (node (ref "U1") (pin "40") (pinfunction "PA4_40") (pintype "bidirectional"))
    )
    (net (code "50") (name "/LED_TOG_2") (class "Default")
      (node (ref "U1") (pin "41") (pinfunction "PA5_41") (pintype "bidirectional"))
    )
    (net (code "51") (name "/LED_TOG_3") (class "Default")
      (node (ref "U1") (pin "45") (pinfunction "PC5_45") (pintype "bidirectional"))
    )
    (net (code "52") (name "/LED_TOG_4") (class "Default")
      (node (ref "U1") (pin "46") (pinfunction "PB0_46") (pintype "bidirectional"))
    )
    (net (code "53") (name "/LED_TOG_5") (class "Default")
      (node (ref "U1") (pin "48") (pinfunction "PB2_48") (pintype "bidirectional"))
    )
    (net (code "54") (name "/NTC_1") (class "Default")
      (node (ref "R21") (pin "1") (pinfunction "1_1") (pintype "passive"))
    )
    (net (code "55") (name "/NTC_2") (class "Default")
      (node (ref "R22") (pin "1") (pinfunction "1_1") (pintype "passive"))
    )
    (net (code "56") (name "/NTC_3") (class "Default")
      (node (ref "R23") (pin "1") (pinfunction "1_1") (pintype "passive"))
    )
    (net (code "57") (name "/NTC_4") (class "Default")
      (node (ref "R24") (pin "1") (pinfunction "1_1") (pintype "passive"))
    )
    (net (code "58") (name "/NTC_5") (class "Default")
      (node (ref "R25") (pin "1") (pinfunction "1_1") (pintype "passive"))
    )
    (net (code "59") (name "/OSC_IN") (class "Default")
      (node (ref "C77") (pin "2") (pinfunction "2_2") (pintype "passive"))
      (node (ref "U1") (pin "23") (pinfunction "PH0-OSC_IN_23") (pintype "bidirectional"))
      (node (ref "Y2") (pin "2") (pinfunction "2_2") (pintype "passive"))
    )
    (net (code "60") (name "/OSC_OUT") (class "Default")
      (node (ref "C78") (pin "2") (pinfunction "2_2") (pintype "passive"))
      (node (ref "U1") (pin "24") (pinfunction "PH1-OSC_OUT_24") (pintype "bidirectional"))
      (node (ref "Y2") (pin "1") (pinfunction "1_1") (pintype "passive"))
    )
    (net (code "61") (name "/OUTPUT_CONNECTED") (class "Default")
      (node (ref "R77") (pin "1") (pinfunction "1_1") (pintype "passive"))
      (node (ref "U1") (pin "80") (pinfunction "PD11_80") (pintype "bidirectional"))
    )
    (net (code "62") (name "/SCL1") (class "Default")
      (node (ref "R49") (pin "1") (pinfunction "1_1") (pintype "passive"))
      (node (ref "R78") (pin "2") (pinfunction "2_2") (pintype "passive"))
      (node (ref "U1") (pin "136") (pinfunction "PB6_136") (pintype "bidirectional"))
    )
    (net (code "63") (name "/SCL2") (class "Default")
      (node (ref "J5") (pin "2") (pinfunction "2_2") (pintype "passive"))
      (node (ref "R78") (pin "1") (pinfunction "1_1") (pintype "passive"))
      (node (ref "R80") (pin "1") (pinfunction "1_1") (pintype "passive"))
      (node (ref "U1") (pin "11") (pinfunction "PF1_11") (pintype "bidirectional"))
    )
    (net (code "64") (name "/SDA1") (class "Default")
      (node (ref "R79") (pin "2") (pinfunction "2_2") (pintype "passive"))
      (node (ref "R95") (pin "1") (pinfunction "1_1") (pintype "passive"))
      (node (ref "U1") (pin "137") (pinfunction "PB7_137") (pintype "bidirectional"))
    )
    (net (code "65") (name "/SDA2") (class "Default")
      (node (ref "J5") (pin "3") (pinfunction "3_3") (pintype "passive"))
      (node (ref "R79") (pin "1") (pinfunction "1_1") (pintype "passive"))
      (node (ref "R81") (pin "1") (pinfunction "1_1") (pintype "passive"))
      (node (ref "U1") (pin "10") (pinfunction "PF0_10") (pintype "bidirectional"))
    )
    (net (code "66") (name "/TDI") (class "Default")
      (node (ref "P2") (pin "8") (pinfunction "TDI_8") (pintype "passive"))
      (node (ref "R14") (pin "2") (pinfunction "2_2") (pintype "passive"))
    )
    (net (code "67") (name "/T_CLK") (class "Default")
      (node (ref "P2") (pin "4") (pinfunction "SWCLK/TCK_4") (pintype "passive"))
      (node (ref "U1") (pin "109") (pinfunction "PA14_109") (pintype "bidirectional"))
    )
    (net (code "68") (name "/T_DIO") (class "Default")
      (node (ref "P2") (pin "2") (pinfunction "SWDIO/TMS_2") (pintype "passive"))
      (node (ref "U1") (pin "105") (pinfunction "PA13_105") (pintype "bidirectional"))
    )
    (net (code "69") (name "/T_RST") (class "Default")
      (node (ref "C84") (pin "2") (pinfunction "2_2") (pintype "passive"))
      (node (ref "D8") (pin "1") (pinfunction "C_1") (pintype "passive"))
      (node (ref "P2") (pin "10") (pinfunction "RESETB_10") (pintype "passive"))
      (node (ref "R82") (pin "2") (pinfunction "2_2") (pintype "passive"))
      (node (ref "S1") (pin "1") (pinfunction "1_1") (pintype "passive"))
      (node (ref "U1") (pin "25") (pinfunction "NRST_25") (pintype "bidirectional"))
    )
    (net (code "70") (name "/T_SWO") (class "Default")
      (node (ref "P2") (pin "6") (pinfunction "SWO/TDO_6") (pintype "passive"))
      (node (ref "R15") (pin "2") (pinfunction "2_2") (pintype "passive"))
    )
    (net (code "71") (name "/UART_RX") (class "Default")
      (node (ref "U1") (pin "116") (pinfunction "PD2_116") (pintype "bidirectional"))
    )
    (net (code "72") (name "/UART_TX") (class "Default")
      (node (ref "U1") (pin "113") (pinfunction "PC12_113") (pintype "bidirectional"))
    )
    (net (code "73") (name "/V_BUS_DIV") (class "Default")
      (node (ref "C38") (pin "2") (pinfunction "2_2") (pintype "passive"))
      (node (ref "R92") (pin "2") (pinfunction "2_2") (pintype "passive"))
      (node (ref "U1") (pin "42") (pinfunction "PA6_42") (pintype "bidirectional"))
    )
    (net (code "82") (name "3V3") (class "Default")
      (node (ref "C10") (pin "2") (pinfunction "2_2") (pintype "passive"))
      (node (ref "C11") (pin "2") (pinfunction "2_2") (pintype "passive"))
      (node (ref "C12") (pin "2") (pinfunction "2_2") (pintype "passive"))
      (node (ref "C13") (pin "2") (pinfunction "2_2") (pintype "passive"))
      (node (ref "C14") (pin "2") (pinfunction "2_2") (pintype "passive"))
      (node (ref "C15") (pin "2") (pinfunction "2_2") (pintype "passive"))
      (node (ref "C16") (pin "2") (pinfunction "2_2") (pintype "passive"))
      (node (ref "C3") (pin "2") (pinfunction "2_2") (pintype "passive"))
      (node (ref "C4") (pin "2") (pinfunction "2_2") (pintype "passive"))
      (node (ref "C5") (pin "2") (pinfunction "2_2") (pintype "passive"))
      (node (ref "C6") (pin "2") (pinfunction "2_2") (pintype "passive"))
      (node (ref "C7") (pin "2") (pinfunction "2_2") (pintype "passive"))
      (node (ref "C8") (pin "2") (pinfunction "2_2") (pintype "passive"))
      (node (ref "C9") (pin "2") (pinfunction "2_2") (pintype "passive"))
      (node (ref "C94") (pin "2") (pinfunction "2_2") (pintype "passive"))
      (node (ref "J5") (pin "1") (pinfunction "1_1") (pintype "passive"))
      (node (ref "P2") (pin "1") (pinfunction "VCC_1") (pintype "passive"))
      (node (ref "R1") (pin "1") (pinfunction "1_1") (pintype "passive"))
      (node (ref "R48") (pin "2") (pinfunction "2_2") (pintype "passive"))
      (node (ref "R49") (pin "2") (pinfunction "2_2") (pintype "passive"))
      (node (ref "R66") (pin "1") (pinfunction "1_1") (pintype "passive"))
      (node (ref "R80") (pin "2") (pinfunction "2_2") (pintype "passive"))
      (node (ref "R81") (pin "2") (pinfunction "2_2") (pintype "passive"))
      (node (ref "R95") (pin "2") (pinfunction "2_2") (pintype "passive"))
      (node (ref "R96") (pin "2") (pinfunction "2_2") (pintype "passive"))
      (node (ref "U1") (pin "108") (pinfunction "VDD_108") (pintype "power_in"))
      (node (ref "U1") (pin "121") (pinfunction "VDD_121") (pintype "power_in"))
      (node (ref "U1") (pin "131") (pinfunction "VDD_131") (pintype "power_in"))
      (node (ref "U1") (pin "144") (pinfunction "VDD_144") (pintype "power_in"))
      (node (ref "U1") (pin "17") (pinfunction "VDD_17") (pintype "power_in"))
      (node (ref "U1") (pin "30") (pinfunction "VDD_30") (pintype "power_in"))
      (node (ref "U1") (pin "33") (pinfunction "VDDA_33") (pintype "power_in"))
      (node (ref "U1") (pin "39") (pinfunction "VDD_39") (pintype "power_in"))
      (node (ref "U1") (pin "52") (pinfunction "VDD_52") (pintype "power_in"))
      (node (ref "U1") (pin "6") (pinfunction "VBAT_6") (pintype "power_in"))
      (node (ref "U1") (pin "62") (pinfunction "VDD_62") (pintype "power_in"))
      (node (ref "U1") (pin "72") (pinfunction "VDD_72") (pintype "power_in"))
      (node (ref "U1") (pin "84") (pinfunction "VDD_84") (pintype "power_in"))
      (node (ref "U1") (pin "95") (pinfunction "VDD33USB_95") (pintype "power_in"))
      (node (ref "U17") (pin "6") (pinfunction "V+_6") (pintype "power_in"))
    )
    (net (code "83") (name "GND") (class "Default")
      (node (ref "C1") (pin "2") (pinfunction "2_2") (pintype "passive"))
      (node (ref "C10") (pin "1") (pinfunction "1_1") (pintype "passive"))
      (node (ref "C11") (pin "1") (pinfunction "1_1") (pintype "passive"))
      (node (ref "C12") (pin "1") (pinfunction "1_1") (pintype "passive"))
      (node (ref "C13") (pin "1") (pinfunction "1_1") (pintype "passive"))
      (node (ref "C14") (pin "1") (pinfunction "1_1") (pintype "passive"))
      (node (ref "C15") (pin "1") (pinfunction "1_1") (pintype "passive"))
      (node (ref "C16") (pin "1") (pinfunction "1_1") (pintype "passive"))
      (node (ref "C17") (pin "1") (pinfunction "1_1") (pintype "passive"))
      (node (ref "C18") (pin "1") (pinfunction "1_1") (pintype "passive"))
      (node (ref "C2") (pin "2") (pinfunction "2_2") (pintype "passive"))
      (node (ref "C3") (pin "1") (pinfunction "1_1") (pintype "passive"))
      (node (ref "C38") (pin "1") (pinfunction "1_1") (pintype "passive"))
      (node (ref "C4") (pin "1") (pinfunction "1_1") (pintype "passive"))
      (node (ref "C5") (pin "1") (pinfunction "1_1") (pintype "passive"))
      (node (ref "C6") (pin "1") (pinfunction "1_1") (pintype "passive"))
      (node (ref "C7") (pin "1") (pinfunction "1_1") (pintype "passive"))
      (node (ref "C76") (pin "1") (pinfunction "1_1") (pintype "passive"))
      (node (ref "C77") (pin "1") (pinfunction "1_1") (pintype "passive"))
      (node (ref "C78") (pin "1") (pinfunction "1_1") (pintype "passive"))
      (node (ref "C8") (pin "1") (pinfunction "1_1") (pintype "passive"))
      (node (ref "C84") (pin "1") (pinfunction "1_1") (pintype "passive"))
      (node (ref "C89") (pin "1") (pinfunction "1_1") (pintype "passive"))
      (node (ref "C9") (pin "1") (pinfunction "1_1") (pintype "passive"))
      (node (ref "C90") (pin "1") (pinfunction "1_1") (pintype "passive"))
      (node (ref "C91") (pin "1") (pinfunction "1_1") (pintype "passive"))
      (node (ref "C92") (pin "1") (pinfunction "1_1") (pintype "passive"))
      (node (ref "C93") (pin "1") (pinfunction "1_1") (pintype "passive"))
      (node (ref "C94") (pin "1") (pinfunction "1_1") (pintype "passive"))
      (node (ref "D12") (pin "K") (pinfunction "K_K") (pintype "passive"))
      (node (ref "D13") (pin "K") (pinfunction "K_K") (pintype "passive"))
      (node (ref "D14") (pin "K") (pinfunction "K_K") (pintype "passive"))
      (node (ref "D8") (pin "2") (pinfunction "A_2") (pintype "passive"))
      (node (ref "J5") (pin "4") (pinfunction "4_4") (pintype "passive"))
      (node (ref "P2") (pin "3") (pinfunction "GND_3") (pintype "passive"))
      (node (ref "P2") (pin "5") (pinfunction "GND_5") (pintype "passive"))
      (node (ref "P2") (pin "9") (pinfunction "GND_9") (pintype "passive"))
      (node (ref "R65") (pin "2") (pinfunction "2_2") (pintype "passive"))
      (node (ref "R67") (pin "2") (pinfunction "2_2") (pintype "passive"))
      (node (ref "R93") (pin "1") (pinfunction "1_1") (pintype "passive"))
      (node (ref "R94") (pin "1") (pinfunction "1_1") (pintype "passive"))
      (node (ref "S1") (pin "2") (pinfunction "2_2") (pintype "passive"))
      (node (ref "U1") (pin "107") (pinfunction "VSS_107") (pintype "power_in"))
      (node (ref "U1") (pin "120") (pinfunction "VSS_120") (pintype "power_in"))
      (node (ref "U1") (pin "130") (pinfunction "VSS_130") (pintype "power_in"))
      (node (ref "U1") (pin "16") (pinfunction "VSS_16") (pintype "power_in"))
      (node (ref "U1") (pin "31") (pinfunction "VSSA_31") (pintype "power_in"))
      (node (ref "U1") (pin "38") (pinfunction "VSS_38") (pintype "power_in"))
      (node (ref "U1") (pin "51") (pinfunction "VSS_51") (pintype "power_in"))
      (node (ref "U1") (pin "61") (pinfunction "VSS_61") (pintype "power_in"))
      (node (ref "U1") (pin "83") (pinfunction "VSS_83") (pintype "power_in"))
      (node (ref "U1") (pin "94") (pinfunction "VSS_94") (pintype "power_in"))
      (node (ref "U17") (pin "2") (pinfunction "V-_2") (pintype "power_in"))
    )
    (net (code "84") (name "Net-(D12-PadA)") (class "Default")
      (node (ref "D12") (pin "A") (pinfunction "A_A") (pintype "passive"))
      (node (ref "R75") (pin "2") (pinfunction "2_2") (pintype "passive"))
    )
    (net (code "85") (name "Net-(D13-PadA)") (class "Default")
      (node (ref "D13") (pin "A") (pinfunction "A_A") (pintype "passive"))
      (node (ref "R76") (pin "1") (pinfunction "1_1") (pintype "passive"))
    )
    (net (code "86") (name "Net-(D14-PadA)") (class "Default")
      (node (ref "D14") (pin "A") (pinfunction "A_A") (pintype "passive"))
      (node (ref "R77") (pin "2") (pinfunction "2_2") (pintype "passive"))
    )
    (net (code "87") (name "Net-(R32-Pad1)") (class "Default")
      (node (ref "R32") (pin "1") (pinfunction "1_1") (pintype "passive"))
      (node (ref "R92") (pin "1") (pinfunction "1_1") (pintype "passive"))
      (node (ref "R93") (pin "2") (pinfunction "2_2") (pintype "passive"))
    )
    (net (code "88") (name "Net-(U1A-PB4)") (class "Default")
      (node (ref "R82") (pin "1") (pinfunction "1_1") (pintype "passive"))
      (node (ref "U1") (pin "134") (pinfunction "PB4_134") (pintype "bidirectional"))
    )
    (net (code "89") (name "Net-(U1B-BOOT0)") (class "Default")
      (node (ref "R65") (pin "1") (pinfunction "1_1") (pintype "passive"))
      (node (ref "U1") (pin "138") (pinfunction "BOOT0_138") (pintype "input"))
    )
    (net (code "90") (name "Net-(U1B-PDR_ON)") (class "Default")
      (node (ref "R66") (pin "2") (pinfunction "2_2") (pintype "passive"))
      (node (ref "R67") (pin "1") (pinfunction "1_1") (pintype "passive"))
      (node (ref "U1") (pin "143") (pinfunction "PDR_ON_143") (pintype "passive"))
    )
    (net (code "91") (name "Net-(U1C-VCAP1)") (class "Default")
      (node (ref "C1") (pin "1") (pinfunction "1_1") (pintype "passive"))
      (node (ref "C2") (pin "1") (pinfunction "1_1") (pintype "passive"))
      (node (ref "U1") (pin "106") (pinfunction "VCAP2_106") (pintype "power_in"))
      (node (ref "U1") (pin "71") (pinfunction "VCAP1_71") (pintype "power_in"))
    )
    (net (code "92") (name "Net-(U17-IN+)") (class "Default")
      (node (ref "C93") (pin "2") (pinfunction "2_2") (pintype "passive"))
      (node (ref "R31") (pin "1") (pinfunction "1_1") (pintype "passive"))
      (node (ref "R94") (pin "2") (pinfunction "2_2") (pintype "passive"))
      (node (ref "U17") (pin "3") (pinfunction "IN+_3") (pintype "tri_state"))
    )
    (net (code "93") (name "Net-(U17-IN-)") (class "Default")
      (node (ref "U17") (pin "4") (pinfunction "IN-_4") (pintype "tri_state"))
      (node (ref "U17") (pin "5") (pinfunction "REF_5") (pintype "passive"))
    )
    (net (code "94") (name "VREF_P") (class "Default")
      (node (ref "C17") (pin "2") (pinfunction "2_2") (pintype "passive"))
      (node (ref "C18") (pin "2") (pinfunction "2_2") (pintype "passive"))
      (node (ref "R1") (pin "2") (pinfunction "2_2") (pintype "passive"))
      (node (ref "U1") (pin "32") (pinfunction "VREF+_32") (pintype "power_in"))
    )
    (net (code "95") (name "V_BAT") (class "Default")
      (node (ref "R31") (pin "2") (pinfunction "2_2") (pintype "passive"))
      (node (ref "R32") (pin "2") (pinfunction "2_2") (pintype "passive"))
    )
    (net (code "96") (name "unconnected-(P2-N{slash}C-Pad7)") (class "Default")
      (node (ref "P2") (pin "7") (pinfunction "N/C_7") (pintype "passive+no_connect"))
    )
    (net (code "97") (name "unconnected-(U1A-PA0-WKUP-Pad34)") (class "Default")
      (node (ref "U1") (pin "34") (pinfunction "PA0-WKUP_34") (pintype "bidirectional+no_connect"))
    )
    (net (code "98") (name "unconnected-(U1A-PA1-Pad35)") (class "Default")
      (node (ref "U1") (pin "35") (pinfunction "PA1_35") (pintype "bidirectional+no_connect"))
    )
    (net (code "99") (name "unconnected-(U1A-PA2-Pad36)") (class "Default")
      (node (ref "U1") (pin "36") (pinfunction "PA2_36") (pintype "bidirectional+no_connect"))
    )
    (net (code "100") (name "unconnected-(U1A-PA3-Pad37)") (class "Default")
      (node (ref "U1") (pin "37") (pinfunction "PA3_37") (pintype "bidirectional+no_connect"))
    )
    (net (code "101") (name "unconnected-(U1A-PB8-Pad139)") (class "Default")
      (node (ref "U1") (pin "139") (pinfunction "PB8_139") (pintype "bidirectional+no_connect"))
    )
    (net (code "102") (name "unconnected-(U1A-PB9-Pad140)") (class "Default")
      (node (ref "U1") (pin "140") (pinfunction "PB9_140") (pintype "bidirectional+no_connect"))
    )
    (net (code "103") (name "unconnected-(U1A-PB10-Pad69)") (class "Default")
      (node (ref "U1") (pin "69") (pinfunction "PB10_69") (pintype "bidirectional+no_connect"))
    )
    (net (code "104") (name "unconnected-(U1A-PB11-Pad70)") (class "Default")
      (node (ref "U1") (pin "70") (pinfunction "PB11_70") (pintype "bidirectional+no_connect"))
    )
    (net (code "105") (name "unconnected-(U1A-PB14-Pad75)") (class "Default")
      (node (ref "U1") (pin "75") (pinfunction "PB14_75") (pintype "bidirectional+no_connect"))
    )
    (net (code "106") (name "unconnected-(U1A-PB15-Pad76)") (class "Default")
      (node (ref "U1") (pin "76") (pinfunction "PB15_76") (pintype "bidirectional+no_connect"))
    )
    (net (code "107") (name "unconnected-(U1A-PC0-Pad26)") (class "Default")
      (node (ref "U1") (pin "26") (pinfunction "PC0_26") (pintype "bidirectional+no_connect"))
    )
    (net (code "108") (name "unconnected-(U1A-PC1-Pad27)") (class "Default")
      (node (ref "U1") (pin "27") (pinfunction "PC1_27") (pintype "bidirectional+no_connect"))
    )
    (net (code "109") (name "unconnected-(U1A-PC2_C-Pad28)") (class "Default")
      (node (ref "U1") (pin "28") (pinfunction "PC2_C_28") (pintype "bidirectional+no_connect"))
    )
    (net (code "110") (name "unconnected-(U1A-PC3_C-Pad29)") (class "Default")
      (node (ref "U1") (pin "29") (pinfunction "PC3_C_29") (pintype "bidirectional+no_connect"))
    )
    (net (code "111") (name "unconnected-(U1A-PC9-Pad99)") (class "Default")
      (node (ref "U1") (pin "99") (pinfunction "PC9_99") (pintype "bidirectional+no_connect"))
    )
    (net (code "112") (name "unconnected-(U1A-PC13-Pad7)") (class "Default")
      (node (ref "U1") (pin "7") (pinfunction "PC13_7") (pintype "bidirectional+no_connect"))
    )
    (net (code "113") (name "unconnected-(U1A-PC14-OSC32_IN-Pad8)") (class "Default")
      (node (ref "U1") (pin "8") (pinfunction "PC14-OSC32_IN_8") (pintype "bidirectional+no_connect"))
    )
    (net (code "114") (name "unconnected-(U1A-PC15-OSC32_OUT-Pad9)") (class "Default")
      (node (ref "U1") (pin "9") (pinfunction "PC15-OSC32_OUT_9") (pintype "bidirectional+no_connect"))
    )
    (net (code "115") (name "unconnected-(U1A-PD3-Pad117)") (class "Default")
      (node (ref "U1") (pin "117") (pinfunction "PD3_117") (pintype "bidirectional+no_connect"))
    )
    (net (code "116") (name "unconnected-(U1A-PD6-Pad122)") (class "Default")
      (node (ref "U1") (pin "122") (pinfunction "PD6_122") (pintype "bidirectional"))
    )
    (net (code "117") (name "unconnected-(U1A-PD7-Pad123)") (class "Default")
      (node (ref "U1") (pin "123") (pinfunction "PD7_123") (pintype "bidirectional"))
    )
    (net (code "118") (name "unconnected-(U1A-PD8-Pad77)") (class "Default")
      (node (ref "U1") (pin "77") (pinfunction "PD8_77") (pintype "bidirectional+no_connect"))
    )
    (net (code "119") (name "unconnected-(U1A-PD12-Pad81)") (class "Default")
      (node (ref "U1") (pin "81") (pinfunction "PD12_81") (pintype "bidirectional+no_connect"))
    )
    (net (code "120") (name "unconnected-(U1A-PD13-Pad82)") (class "Default")
      (node (ref "U1") (pin "82") (pinfunction "PD13_82") (pintype "bidirectional+no_connect"))
    )
    (net (code "121") (name "unconnected-(U1A-PD14-Pad85)") (class "Default")
      (node (ref "U1") (pin "85") (pinfunction "PD14_85") (pintype "bidirectional+no_connect"))
    )
    (net (code "122") (name "unconnected-(U1A-PD15-Pad86)") (class "Default")
      (node (ref "U1") (pin "86") (pinfunction "PD15_86") (pintype "bidirectional+no_connect"))
    )
    (net (code "123") (name "unconnected-(U1B-PE0-Pad141)") (class "Default")
      (node (ref "U1") (pin "141") (pinfunction "PE0_141") (pintype "bidirectional+no_connect"))
    )
    (net (code "124") (name "unconnected-(U1B-PE1-Pad142)") (class "Default")
      (node (ref "U1") (pin "142") (pinfunction "PE1_142") (pintype "bidirectional+no_connect"))
    )
    (net (code "125") (name "unconnected-(U1B-PE2-Pad1)") (class "Default")
      (node (ref "U1") (pin "1") (pinfunction "PE2_1") (pintype "bidirectional+no_connect"))
    )
    (net (code "126") (name "unconnected-(U1B-PE3-Pad2)") (class "Default")
      (node (ref "U1") (pin "2") (pinfunction "PE3_2") (pintype "bidirectional+no_connect"))
    )
    (net (code "127") (name "unconnected-(U1B-PE4-Pad3)") (class "Default")
      (node (ref "U1") (pin "3") (pinfunction "PE4_3") (pintype "bidirectional+no_connect"))
    )
    (net (code "128") (name "unconnected-(U1B-PE5-Pad4)") (class "Default")
      (node (ref "U1") (pin "4") (pinfunction "PE5_4") (pintype "bidirectional+no_connect"))
    )
    (net (code "129") (name "unconnected-(U1B-PE6-Pad5)") (class "Default")
      (node (ref "U1") (pin "5") (pinfunction "PE6_5") (pintype "bidirectional+no_connect"))
    )
    (net (code "130") (name "unconnected-(U1B-PE7-Pad58)") (class "Default")
      (node (ref "U1") (pin "58") (pinfunction "PE7_58") (pintype "bidirectional+no_connect"))
    )
    (net (code "131") (name "unconnected-(U1B-PE8-Pad59)") (class "Default")
      (node (ref "U1") (pin "59") (pinfunction "PE8_59") (pintype "bidirectional+no_connect"))
    )
    (net (code "132") (name "unconnected-(U1B-PE9-Pad60)") (class "Default")
      (node (ref "U1") (pin "60") (pinfunction "PE9_60") (pintype "bidirectional+no_connect"))
    )
    (net (code "133") (name "unconnected-(U1B-PE10-Pad63)") (class "Default")
      (node (ref "U1") (pin "63") (pinfunction "PE10_63") (pintype "bidirectional+no_connect"))
    )
    (net (code "134") (name "unconnected-(U1B-PE11-Pad64)") (class "Default")
      (node (ref "U1") (pin "64") (pinfunction "PE11_64") (pintype "bidirectional+no_connect"))
    )
    (net (code "135") (name "unconnected-(U1B-PE12-Pad65)") (class "Default")
      (node (ref "U1") (pin "65") (pinfunction "PE12_65") (pintype "bidirectional+no_connect"))
    )
    (net (code "136") (name "unconnected-(U1B-PE13-Pad66)") (class "Default")
      (node (ref "U1") (pin "66") (pinfunction "PE13_66") (pintype "bidirectional+no_connect"))
    )
    (net (code "137") (name "unconnected-(U1B-PE14-Pad67)") (class "Default")
      (node (ref "U1") (pin "67") (pinfunction "PE14_67") (pintype "bidirectional+no_connect"))
    )
    (net (code "138") (name "unconnected-(U1B-PE15-Pad68)") (class "Default")
      (node (ref "U1") (pin "68") (pinfunction "PE15_68") (pintype "bidirectional+no_connect"))
    )
    (net (code "139") (name "unconnected-(U1B-PF4-Pad14)") (class "Default")
      (node (ref "U1") (pin "14") (pinfunction "PF4_14") (pintype "bidirectional+no_connect"))
    )
    (net (code "140") (name "unconnected-(U1B-PF6-Pad18)") (class "Default")
      (node (ref "U1") (pin "18") (pinfunction "PF6_18") (pintype "bidirectional+no_connect"))
    )
    (net (code "141") (name "unconnected-(U1B-PF8-Pad20)") (class "Default")
      (node (ref "U1") (pin "20") (pinfunction "PF8_20") (pintype "bidirectional+no_connect"))
    )
    (net (code "142") (name "unconnected-(U1B-PF10-Pad22)") (class "Default")
      (node (ref "U1") (pin "22") (pinfunction "PF10_22") (pintype "bidirectional+no_connect"))
    )
    (net (code "143") (name "unconnected-(U1B-PF14-Pad54)") (class "Default")
      (node (ref "U1") (pin "54") (pinfunction "PF14_54") (pintype "bidirectional+no_connect"))
    )
    (net (code "144") (name "unconnected-(U1B-PF15-Pad55)") (class "Default")
      (node (ref "U1") (pin "55") (pinfunction "PF15_55") (pintype "bidirectional+no_connect"))
    )
    (net (code "145") (name "unconnected-(U1B-PG0-Pad56)") (class "Default")
      (node (ref "U1") (pin "56") (pinfunction "PG0_56") (pintype "bidirectional+no_connect"))
    )
    (net (code "146") (name "unconnected-(U1B-PG1-Pad57)") (class "Default")
      (node (ref "U1") (pin "57") (pinfunction "PG1_57") (pintype "bidirectional+no_connect"))
    )
    (net (code "147") (name "unconnected-(U1B-PG2-Pad87)") (class "Default")
      (node (ref "U1") (pin "87") (pinfunction "PG2_87") (pintype "bidirectional+no_connect"))
    )
    (net (code "148") (name "unconnected-(U1B-PG3-Pad88)") (class "Default")
      (node (ref "U1") (pin "88") (pinfunction "PG3_88") (pintype "bidirectional+no_connect"))
    )
    (net (code "149") (name "unconnected-(U1B-PG4-Pad89)") (class "Default")
      (node (ref "U1") (pin "89") (pinfunction "PG4_89") (pintype "bidirectional+no_connect"))
    )
    (net (code "150") (name "unconnected-(U1B-PG5-Pad90)") (class "Default")
      (node (ref "U1") (pin "90") (pinfunction "PG5_90") (pintype "bidirectional+no_connect"))
    )
    (net (code "151") (name "unconnected-(U1B-PG8-Pad93)") (class "Default")
      (node (ref "U1") (pin "93") (pinfunction "PG8_93") (pintype "bidirectional+no_connect"))
    )
    (net (code "152") (name "unconnected-(U1B-PG9-Pad124)") (class "Default")
      (node (ref "U1") (pin "124") (pinfunction "PG9_124") (pintype "bidirectional"))
    )
    (net (code "153") (name "unconnected-(U1B-PG11-Pad126)") (class "Default")
      (node (ref "U1") (pin "126") (pinfunction "PG11_126") (pintype "bidirectional"))
    )
    (net (code "154") (name "unconnected-(U1B-PG12-Pad127)") (class "Default")
      (node (ref "U1") (pin "127") (pinfunction "PG12_127") (pintype "bidirectional"))
    )
    (net (code "155") (name "unconnected-(U1B-PG13-Pad128)") (class "Default")
      (node (ref "U1") (pin "128") (pinfunction "PG13_128") (pintype "bidirectional"))
    )
    (net (code "156") (name "unconnected-(U1B-PG14-Pad129)") (class "Default")
      (node (ref "U1") (pin "129") (pinfunction "PG14_129") (pintype "bidirectional"))
    )
    (net (code "157") (name "unconnected-(U1B-PG15-Pad132)") (class "Default")
      (node (ref "U1") (pin "132") (pinfunction "PG15_132") (pintype "bidirectional"))
    )
  )
)
